# tcrt_0.net
KiCad netlist of a schematic drawn in Altium Designer
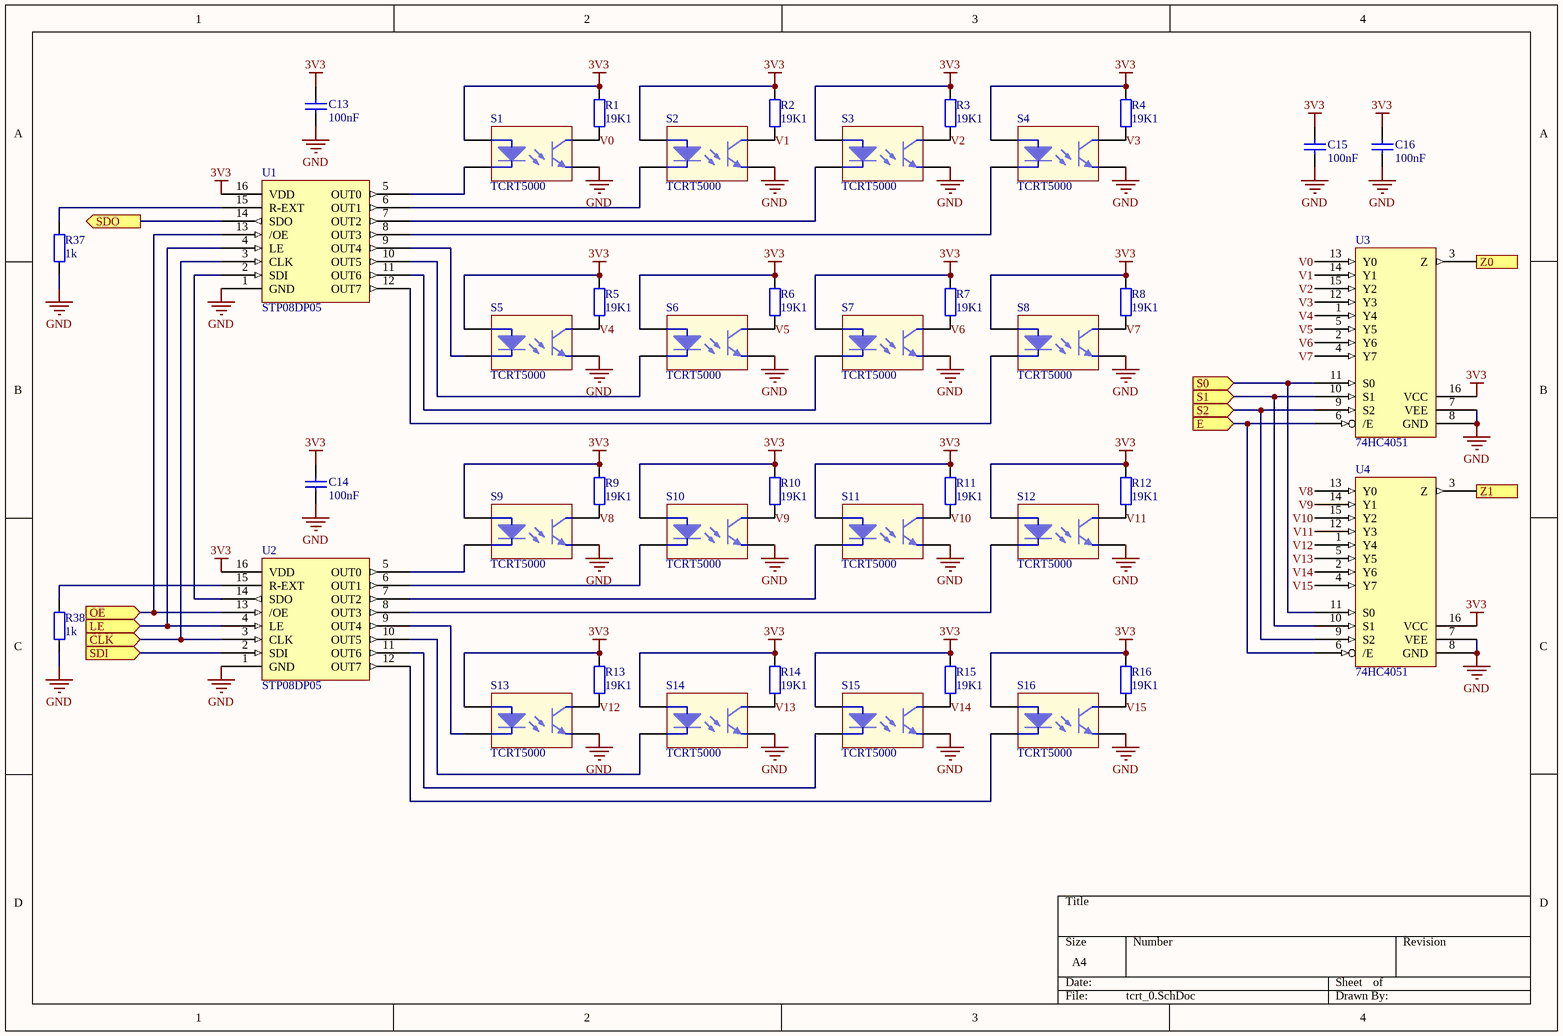
[diagram p0: tcrt_0.SchDoc]

(export (version "E")
  (design (tool "Eeschema 10.0.6"))
  (components
    (comp (ref "C13")
      (value "100nF")
      (footprint "FP_0805_CAP_085")
      (description "Capacitor")
      (libsource (lib "hallglib") (part "CAP"))
    )
    (comp (ref "C14")
      (value "100nF")
      (footprint "FP_0805_CAP_085")
      (description "Capacitor")
      (libsource (lib "hallglib") (part "CAP"))
    )
    (comp (ref "C15")
      (value "100nF")
      (footprint "FP_0805_CAP_085")
      (description "Capacitor")
      (libsource (lib "hallglib") (part "CAP"))
    )
    (comp (ref "C16")
      (value "100nF")
      (footprint "FP_0805_CAP_085")
      (description "Capacitor")
      (libsource (lib "hallglib") (part "CAP"))
    )
    (comp (ref "R1")
      (value "19K1")
      (footprint "FP_0805_RES")
      (description "Resistor")
      (libsource (lib "hallglib") (part "RES"))
    )
    (comp (ref "R2")
      (value "19K1")
      (footprint "FP_0805_RES")
      (description "Resistor")
      (libsource (lib "hallglib") (part "RES"))
    )
    (comp (ref "R3")
      (value "19K1")
      (footprint "FP_0805_RES")
      (description "Resistor")
      (libsource (lib "hallglib") (part "RES"))
    )
    (comp (ref "R4")
      (value "19K1")
      (footprint "FP_0805_RES")
      (description "Resistor")
      (libsource (lib "hallglib") (part "RES"))
    )
    (comp (ref "R5")
      (value "19K1")
      (footprint "FP_0805_RES")
      (description "Resistor")
      (libsource (lib "hallglib") (part "RES"))
    )
    (comp (ref "R6")
      (value "19K1")
      (footprint "FP_0805_RES")
      (description "Resistor")
      (libsource (lib "hallglib") (part "RES"))
    )
    (comp (ref "R7")
      (value "19K1")
      (footprint "FP_0805_RES")
      (description "Resistor")
      (libsource (lib "hallglib") (part "RES"))
    )
    (comp (ref "R8")
      (value "19K1")
      (footprint "FP_0805_RES")
      (description "Resistor")
      (libsource (lib "hallglib") (part "RES"))
    )
    (comp (ref "R9")
      (value "19K1")
      (footprint "FP_0805_RES")
      (description "Resistor")
      (libsource (lib "hallglib") (part "RES"))
    )
    (comp (ref "R10")
      (value "19K1")
      (footprint "FP_0805_RES")
      (description "Resistor")
      (libsource (lib "hallglib") (part "RES"))
    )
    (comp (ref "R11")
      (value "19K1")
      (footprint "FP_0805_RES")
      (description "Resistor")
      (libsource (lib "hallglib") (part "RES"))
    )
    (comp (ref "R12")
      (value "19K1")
      (footprint "FP_0805_RES")
      (description "Resistor")
      (libsource (lib "hallglib") (part "RES"))
    )
    (comp (ref "R13")
      (value "19K1")
      (footprint "FP_0805_RES")
      (description "Resistor")
      (libsource (lib "hallglib") (part "RES"))
    )
    (comp (ref "R14")
      (value "19K1")
      (footprint "FP_0805_RES")
      (description "Resistor")
      (libsource (lib "hallglib") (part "RES"))
    )
    (comp (ref "R15")
      (value "19K1")
      (footprint "FP_0805_RES")
      (description "Resistor")
      (libsource (lib "hallglib") (part "RES"))
    )
    (comp (ref "R16")
      (value "19K1")
      (footprint "FP_0805_RES")
      (description "Resistor")
      (libsource (lib "hallglib") (part "RES"))
    )
    (comp (ref "R37")
      (value "1k")
      (footprint "FP_0805_RES")
      (description "Resistor")
      (libsource (lib "") (part "RES_1"))
    )
    (comp (ref "R38")
      (value "1k")
      (footprint "FP_0805_RES")
      (description "Resistor")
      (libsource (lib "") (part "RES_1"))
    )
    (comp (ref "S1")
      (value "TCRT5000")
      (footprint "TCRT5000_nohole")
      (description "Reflective Optical Sensor")
      (libsource (lib "line-sensor") (part "TCRT5000"))
    )
    (comp (ref "S2")
      (value "TCRT5000")
      (footprint "TCRT5000_nohole")
      (description "Reflective Optical Sensor")
      (libsource (lib "line-sensor") (part "TCRT5000"))
    )
    (comp (ref "S3")
      (value "TCRT5000")
      (footprint "TCRT5000_nohole")
      (description "Reflective Optical Sensor")
      (libsource (lib "line-sensor") (part "TCRT5000"))
    )
    (comp (ref "S4")
      (value "TCRT5000")
      (footprint "TCRT5000_nohole")
      (description "Reflective Optical Sensor")
      (libsource (lib "line-sensor") (part "TCRT5000"))
    )
    (comp (ref "S5")
      (value "TCRT5000")
      (footprint "TCRT5000_nohole")
      (description "Reflective Optical Sensor")
      (libsource (lib "line-sensor") (part "TCRT5000"))
    )
    (comp (ref "S6")
      (value "TCRT5000")
      (footprint "TCRT5000_nohole")
      (description "Reflective Optical Sensor")
      (libsource (lib "line-sensor") (part "TCRT5000"))
    )
    (comp (ref "S7")
      (value "TCRT5000")
      (footprint "TCRT5000_nohole")
      (description "Reflective Optical Sensor")
      (libsource (lib "line-sensor") (part "TCRT5000"))
    )
    (comp (ref "S8")
      (value "TCRT5000")
      (footprint "TCRT5000_nohole")
      (description "Reflective Optical Sensor")
      (libsource (lib "line-sensor") (part "TCRT5000"))
    )
    (comp (ref "S9")
      (value "TCRT5000")
      (footprint "TCRT5000_nohole")
      (description "Reflective Optical Sensor")
      (libsource (lib "line-sensor") (part "TCRT5000"))
    )
    (comp (ref "S10")
      (value "TCRT5000")
      (footprint "TCRT5000_nohole")
      (description "Reflective Optical Sensor")
      (libsource (lib "line-sensor") (part "TCRT5000"))
    )
    (comp (ref "S11")
      (value "TCRT5000")
      (footprint "TCRT5000_nohole")
      (description "Reflective Optical Sensor")
      (libsource (lib "line-sensor") (part "TCRT5000"))
    )
    (comp (ref "S12")
      (value "TCRT5000")
      (footprint "TCRT5000_nohole")
      (description "Reflective Optical Sensor")
      (libsource (lib "line-sensor") (part "TCRT5000"))
    )
    (comp (ref "S13")
      (value "TCRT5000")
      (footprint "TCRT5000_nohole")
      (description "Reflective Optical Sensor")
      (libsource (lib "line-sensor") (part "TCRT5000"))
    )
    (comp (ref "S14")
      (value "TCRT5000")
      (footprint "TCRT5000_nohole")
      (description "Reflective Optical Sensor")
      (libsource (lib "line-sensor") (part "TCRT5000"))
    )
    (comp (ref "S15")
      (value "TCRT5000")
      (footprint "TCRT5000_nohole")
      (description "Reflective Optical Sensor")
      (libsource (lib "line-sensor") (part "TCRT5000"))
    )
    (comp (ref "S16")
      (value "TCRT5000")
      (footprint "TCRT5000_nohole")
      (description "Reflective Optical Sensor")
      (libsource (lib "line-sensor") (part "TCRT5000"))
    )
    (comp (ref "U1")
      (value "STP08DP05")
      (footprint "TSSOP16_2")
      (description "LED driver [8]")
      (libsource (lib "line-sensor") (part "STP08DP05"))
    )
    (comp (ref "U2")
      (value "STP08DP05")
      (footprint "TSSOP16_2")
      (description "LED driver [8]")
      (libsource (lib "line-sensor") (part "STP08DP05"))
    )
    (comp (ref "U3")
      (value "74HC4051")
      (footprint "TSSOP16_2")
      (description "Analog multiplexer")
      (libsource (lib "line-sensor") (part "74HC4051"))
    )
    (comp (ref "U4")
      (value "74HC4051")
      (footprint "TSSOP16_2")
      (description "Analog multiplexer")
      (libsource (lib "line-sensor") (part "74HC4051"))
    )
  )
  (nets
    (net (code "1") (name "/CLK") (class "Default")
      (node (ref "U1") (pin "3") (pinfunction "CLK_3") (pintype "input"))
      (node (ref "U2") (pin "3") (pinfunction "CLK_3") (pintype "input"))
    )
    (net (code "2") (name "/E") (class "Default")
      (node (ref "U3") (pin "6") (pinfunction "/E_6") (pintype "input"))
      (node (ref "U4") (pin "6") (pinfunction "/E_6") (pintype "input"))
    )
    (net (code "3") (name "/LE") (class "Default")
      (node (ref "U1") (pin "4") (pinfunction "LE_4") (pintype "input"))
      (node (ref "U2") (pin "4") (pinfunction "LE_4") (pintype "input"))
    )
    (net (code "4") (name "/OE") (class "Default")
      (node (ref "U1") (pin "13") (pinfunction "/OE_13") (pintype "input"))
      (node (ref "U2") (pin "13") (pinfunction "/OE_13") (pintype "input"))
    )
    (net (code "5") (name "/S0") (class "Default")
      (node (ref "U3") (pin "11") (pinfunction "S0_11") (pintype "input"))
      (node (ref "U4") (pin "11") (pinfunction "S0_11") (pintype "input"))
    )
    (net (code "6") (name "/S1") (class "Default")
      (node (ref "U3") (pin "10") (pinfunction "S1_10") (pintype "input"))
      (node (ref "U4") (pin "10") (pinfunction "S1_10") (pintype "input"))
    )
    (net (code "7") (name "/S2") (class "Default")
      (node (ref "U3") (pin "9") (pinfunction "S2_9") (pintype "input"))
      (node (ref "U4") (pin "9") (pinfunction "S2_9") (pintype "input"))
    )
    (net (code "8") (name "/SDI") (class "Default")
      (node (ref "U2") (pin "2") (pinfunction "SDI_2") (pintype "input"))
    )
    (net (code "9") (name "/SDO") (class "Default")
      (node (ref "U1") (pin "14") (pinfunction "SDO_14") (pintype "output"))
    )
    (net (code "10") (name "/V0") (class "Default")
      (node (ref "R1") (pin "1") (pinfunction "1_1") (pintype "passive"))
      (node (ref "S1") (pin "Coll") (pinfunction "C_Coll") (pintype "passive"))
      (node (ref "U3") (pin "13") (pinfunction "Y0_13") (pintype "input"))
    )
    (net (code "11") (name "/V1") (class "Default")
      (node (ref "R2") (pin "1") (pinfunction "1_1") (pintype "passive"))
      (node (ref "S2") (pin "Coll") (pinfunction "C_Coll") (pintype "passive"))
      (node (ref "U3") (pin "14") (pinfunction "Y1_14") (pintype "input"))
    )
    (net (code "12") (name "/V2") (class "Default")
      (node (ref "R3") (pin "1") (pinfunction "1_1") (pintype "passive"))
      (node (ref "S3") (pin "Coll") (pinfunction "C_Coll") (pintype "passive"))
      (node (ref "U3") (pin "15") (pinfunction "Y2_15") (pintype "input"))
    )
    (net (code "13") (name "/V3") (class "Default")
      (node (ref "R4") (pin "1") (pinfunction "1_1") (pintype "passive"))
      (node (ref "S4") (pin "Coll") (pinfunction "C_Coll") (pintype "passive"))
      (node (ref "U3") (pin "12") (pinfunction "Y3_12") (pintype "input"))
    )
    (net (code "14") (name "/V4") (class "Default")
      (node (ref "R5") (pin "1") (pinfunction "1_1") (pintype "passive"))
      (node (ref "S5") (pin "Coll") (pinfunction "C_Coll") (pintype "passive"))
      (node (ref "U3") (pin "1") (pinfunction "Y4_1") (pintype "input"))
    )
    (net (code "15") (name "/V5") (class "Default")
      (node (ref "R6") (pin "1") (pinfunction "1_1") (pintype "passive"))
      (node (ref "S6") (pin "Coll") (pinfunction "C_Coll") (pintype "passive"))
      (node (ref "U3") (pin "5") (pinfunction "Y5_5") (pintype "input"))
    )
    (net (code "16") (name "/V6") (class "Default")
      (node (ref "R7") (pin "1") (pinfunction "1_1") (pintype "passive"))
      (node (ref "S7") (pin "Coll") (pinfunction "C_Coll") (pintype "passive"))
      (node (ref "U3") (pin "2") (pinfunction "Y6_2") (pintype "input"))
    )
    (net (code "17") (name "/V7") (class "Default")
      (node (ref "R8") (pin "1") (pinfunction "1_1") (pintype "passive"))
      (node (ref "S8") (pin "Coll") (pinfunction "C_Coll") (pintype "passive"))
      (node (ref "U3") (pin "4") (pinfunction "Y7_4") (pintype "input"))
    )
    (net (code "18") (name "/V8") (class "Default")
      (node (ref "R9") (pin "1") (pinfunction "1_1") (pintype "passive"))
      (node (ref "S9") (pin "Coll") (pinfunction "C_Coll") (pintype "passive"))
      (node (ref "U4") (pin "13") (pinfunction "Y0_13") (pintype "input"))
    )
    (net (code "19") (name "/V9") (class "Default")
      (node (ref "R10") (pin "1") (pinfunction "1_1") (pintype "passive"))
      (node (ref "S10") (pin "Coll") (pinfunction "C_Coll") (pintype "passive"))
      (node (ref "U4") (pin "14") (pinfunction "Y1_14") (pintype "input"))
    )
    (net (code "20") (name "/V10") (class "Default")
      (node (ref "R11") (pin "1") (pinfunction "1_1") (pintype "passive"))
      (node (ref "S11") (pin "Coll") (pinfunction "C_Coll") (pintype "passive"))
      (node (ref "U4") (pin "15") (pinfunction "Y2_15") (pintype "input"))
    )
    (net (code "21") (name "/V11") (class "Default")
      (node (ref "R12") (pin "1") (pinfunction "1_1") (pintype "passive"))
      (node (ref "S12") (pin "Coll") (pinfunction "C_Coll") (pintype "passive"))
      (node (ref "U4") (pin "12") (pinfunction "Y3_12") (pintype "input"))
    )
    (net (code "22") (name "/V12") (class "Default")
      (node (ref "R13") (pin "1") (pinfunction "1_1") (pintype "passive"))
      (node (ref "S13") (pin "Coll") (pinfunction "C_Coll") (pintype "passive"))
      (node (ref "U4") (pin "1") (pinfunction "Y4_1") (pintype "input"))
    )
    (net (code "23") (name "/V13") (class "Default")
      (node (ref "R14") (pin "1") (pinfunction "1_1") (pintype "passive"))
      (node (ref "S14") (pin "Coll") (pinfunction "C_Coll") (pintype "passive"))
      (node (ref "U4") (pin "5") (pinfunction "Y5_5") (pintype "input"))
    )
    (net (code "24") (name "/V14") (class "Default")
      (node (ref "R15") (pin "1") (pinfunction "1_1") (pintype "passive"))
      (node (ref "S15") (pin "Coll") (pinfunction "C_Coll") (pintype "passive"))
      (node (ref "U4") (pin "2") (pinfunction "Y6_2") (pintype "input"))
    )
    (net (code "25") (name "/V15") (class "Default")
      (node (ref "R16") (pin "1") (pinfunction "1_1") (pintype "passive"))
      (node (ref "S16") (pin "Coll") (pinfunction "C_Coll") (pintype "passive"))
      (node (ref "U4") (pin "4") (pinfunction "Y7_4") (pintype "input"))
    )
    (net (code "26") (name "/Z0") (class "Default")
      (node (ref "U3") (pin "3") (pinfunction "Z_3") (pintype "output"))
    )
    (net (code "27") (name "/Z1") (class "Default")
      (node (ref "U4") (pin "3") (pinfunction "Z_3") (pintype "output"))
    )
    (net (code "28") (name "3V3") (class "Default")
      (node (ref "C13") (pin "2") (pinfunction "2_2") (pintype "passive"))
      (node (ref "C14") (pin "2") (pinfunction "2_2") (pintype "passive"))
      (node (ref "C15") (pin "2") (pinfunction "2_2") (pintype "passive"))
      (node (ref "C16") (pin "2") (pinfunction "2_2") (pintype "passive"))
      (node (ref "R1") (pin "2") (pinfunction "2_2") (pintype "passive"))
      (node (ref "R10") (pin "2") (pinfunction "2_2") (pintype "passive"))
      (node (ref "R11") (pin "2") (pinfunction "2_2") (pintype "passive"))
      (node (ref "R12") (pin "2") (pinfunction "2_2") (pintype "passive"))
      (node (ref "R13") (pin "2") (pinfunction "2_2") (pintype "passive"))
      (node (ref "R14") (pin "2") (pinfunction "2_2") (pintype "passive"))
      (node (ref "R15") (pin "2") (pinfunction "2_2") (pintype "passive"))
      (node (ref "R16") (pin "2") (pinfunction "2_2") (pintype "passive"))
      (node (ref "R2") (pin "2") (pinfunction "2_2") (pintype "passive"))
      (node (ref "R3") (pin "2") (pinfunction "2_2") (pintype "passive"))
      (node (ref "R4") (pin "2") (pinfunction "2_2") (pintype "passive"))
      (node (ref "R5") (pin "2") (pinfunction "2_2") (pintype "passive"))
      (node (ref "R6") (pin "2") (pinfunction "2_2") (pintype "passive"))
      (node (ref "R7") (pin "2") (pinfunction "2_2") (pintype "passive"))
      (node (ref "R8") (pin "2") (pinfunction "2_2") (pintype "passive"))
      (node (ref "R9") (pin "2") (pinfunction "2_2") (pintype "passive"))
      (node (ref "S1") (pin "A") (pinfunction "A_A") (pintype "passive"))
      (node (ref "S10") (pin "A") (pinfunction "A_A") (pintype "passive"))
      (node (ref "S11") (pin "A") (pinfunction "A_A") (pintype "passive"))
      (node (ref "S12") (pin "A") (pinfunction "A_A") (pintype "passive"))
      (node (ref "S13") (pin "A") (pinfunction "A_A") (pintype "passive"))
      (node (ref "S14") (pin "A") (pinfunction "A_A") (pintype "passive"))
      (node (ref "S15") (pin "A") (pinfunction "A_A") (pintype "passive"))
      (node (ref "S16") (pin "A") (pinfunction "A_A") (pintype "passive"))
      (node (ref "S2") (pin "A") (pinfunction "A_A") (pintype "passive"))
      (node (ref "S3") (pin "A") (pinfunction "A_A") (pintype "passive"))
      (node (ref "S4") (pin "A") (pinfunction "A_A") (pintype "passive"))
      (node (ref "S5") (pin "A") (pinfunction "A_A") (pintype "passive"))
      (node (ref "S6") (pin "A") (pinfunction "A_A") (pintype "passive"))
      (node (ref "S7") (pin "A") (pinfunction "A_A") (pintype "passive"))
      (node (ref "S8") (pin "A") (pinfunction "A_A") (pintype "passive"))
      (node (ref "S9") (pin "A") (pinfunction "A_A") (pintype "passive"))
      (node (ref "U1") (pin "16") (pinfunction "VDD_16") (pintype "passive"))
      (node (ref "U2") (pin "16") (pinfunction "VDD_16") (pintype "passive"))
      (node (ref "U3") (pin "16") (pinfunction "VCC_16") (pintype "power_in"))
      (node (ref "U4") (pin "16") (pinfunction "VCC_16") (pintype "power_in"))
    )
    (net (code "29") (name "GND") (class "Default")
      (node (ref "C13") (pin "1") (pinfunction "1_1") (pintype "passive"))
      (node (ref "C14") (pin "1") (pinfunction "1_1") (pintype "passive"))
      (node (ref "C15") (pin "1") (pinfunction "1_1") (pintype "passive"))
      (node (ref "C16") (pin "1") (pinfunction "1_1") (pintype "passive"))
      (node (ref "R37") (pin "2") (pinfunction "2_2") (pintype "passive"))
      (node (ref "R38") (pin "2") (pinfunction "2_2") (pintype "passive"))
      (node (ref "S1") (pin "E") (pinfunction "E_E") (pintype "passive"))
      (node (ref "S10") (pin "E") (pinfunction "E_E") (pintype "passive"))
      (node (ref "S11") (pin "E") (pinfunction "E_E") (pintype "passive"))
      (node (ref "S12") (pin "E") (pinfunction "E_E") (pintype "passive"))
      (node (ref "S13") (pin "E") (pinfunction "E_E") (pintype "passive"))
      (node (ref "S14") (pin "E") (pinfunction "E_E") (pintype "passive"))
      (node (ref "S15") (pin "E") (pinfunction "E_E") (pintype "passive"))
      (node (ref "S16") (pin "E") (pinfunction "E_E") (pintype "passive"))
      (node (ref "S2") (pin "E") (pinfunction "E_E") (pintype "passive"))
      (node (ref "S3") (pin "E") (pinfunction "E_E") (pintype "passive"))
      (node (ref "S4") (pin "E") (pinfunction "E_E") (pintype "passive"))
      (node (ref "S5") (pin "E") (pinfunction "E_E") (pintype "passive"))
      (node (ref "S6") (pin "E") (pinfunction "E_E") (pintype "passive"))
      (node (ref "S7") (pin "E") (pinfunction "E_E") (pintype "passive"))
      (node (ref "S8") (pin "E") (pinfunction "E_E") (pintype "passive"))
      (node (ref "S9") (pin "E") (pinfunction "E_E") (pintype "passive"))
      (node (ref "U1") (pin "1") (pinfunction "GND_1") (pintype "power_in"))
      (node (ref "U2") (pin "1") (pinfunction "GND_1") (pintype "power_in"))
      (node (ref "U3") (pin "7") (pinfunction "VEE_7") (pintype "power_in"))
      (node (ref "U3") (pin "8") (pinfunction "GND_8") (pintype "power_in"))
      (node (ref "U4") (pin "7") (pinfunction "VEE_7") (pintype "power_in"))
      (node (ref "U4") (pin "8") (pinfunction "GND_8") (pintype "power_in"))
    )
    (net (code "30") (name "Net-(S1-K)") (class "Default")
      (node (ref "S1") (pin "Cath") (pinfunction "K_Cath") (pintype "passive"))
      (node (ref "U1") (pin "5") (pinfunction "OUT0_5") (pintype "output"))
    )
    (net (code "31") (name "Net-(S2-K)") (class "Default")
      (node (ref "S2") (pin "Cath") (pinfunction "K_Cath") (pintype "passive"))
      (node (ref "U1") (pin "6") (pinfunction "OUT1_6") (pintype "output"))
    )
    (net (code "32") (name "Net-(S3-K)") (class "Default")
      (node (ref "S3") (pin "Cath") (pinfunction "K_Cath") (pintype "passive"))
      (node (ref "U1") (pin "7") (pinfunction "OUT2_7") (pintype "output"))
    )
    (net (code "33") (name "Net-(S4-K)") (class "Default")
      (node (ref "S4") (pin "Cath") (pinfunction "K_Cath") (pintype "passive"))
      (node (ref "U1") (pin "8") (pinfunction "OUT3_8") (pintype "output"))
    )
    (net (code "34") (name "Net-(S5-K)") (class "Default")
      (node (ref "S5") (pin "Cath") (pinfunction "K_Cath") (pintype "passive"))
      (node (ref "U1") (pin "9") (pinfunction "OUT4_9") (pintype "output"))
    )
    (net (code "35") (name "Net-(S6-K)") (class "Default")
      (node (ref "S6") (pin "Cath") (pinfunction "K_Cath") (pintype "passive"))
      (node (ref "U1") (pin "10") (pinfunction "OUT5_10") (pintype "output"))
    )
    (net (code "36") (name "Net-(S7-K)") (class "Default")
      (node (ref "S7") (pin "Cath") (pinfunction "K_Cath") (pintype "passive"))
      (node (ref "U1") (pin "11") (pinfunction "OUT6_11") (pintype "output"))
    )
    (net (code "37") (name "Net-(S8-K)") (class "Default")
      (node (ref "S8") (pin "Cath") (pinfunction "K_Cath") (pintype "passive"))
      (node (ref "U1") (pin "12") (pinfunction "OUT7_12") (pintype "output"))
    )
    (net (code "38") (name "Net-(S9-K)") (class "Default")
      (node (ref "S9") (pin "Cath") (pinfunction "K_Cath") (pintype "passive"))
      (node (ref "U2") (pin "5") (pinfunction "OUT0_5") (pintype "output"))
    )
    (net (code "39") (name "Net-(S10-K)") (class "Default")
      (node (ref "S10") (pin "Cath") (pinfunction "K_Cath") (pintype "passive"))
      (node (ref "U2") (pin "6") (pinfunction "OUT1_6") (pintype "output"))
    )
    (net (code "40") (name "Net-(S11-K)") (class "Default")
      (node (ref "S11") (pin "Cath") (pinfunction "K_Cath") (pintype "passive"))
      (node (ref "U2") (pin "7") (pinfunction "OUT2_7") (pintype "output"))
    )
    (net (code "41") (name "Net-(S12-K)") (class "Default")
      (node (ref "S12") (pin "Cath") (pinfunction "K_Cath") (pintype "passive"))
      (node (ref "U2") (pin "8") (pinfunction "OUT3_8") (pintype "output"))
    )
    (net (code "42") (name "Net-(S13-K)") (class "Default")
      (node (ref "S13") (pin "Cath") (pinfunction "K_Cath") (pintype "passive"))
      (node (ref "U2") (pin "9") (pinfunction "OUT4_9") (pintype "output"))
    )
    (net (code "43") (name "Net-(S14-K)") (class "Default")
      (node (ref "S14") (pin "Cath") (pinfunction "K_Cath") (pintype "passive"))
      (node (ref "U2") (pin "10") (pinfunction "OUT5_10") (pintype "output"))
    )
    (net (code "44") (name "Net-(S15-K)") (class "Default")
      (node (ref "S15") (pin "Cath") (pinfunction "K_Cath") (pintype "passive"))
      (node (ref "U2") (pin "11") (pinfunction "OUT6_11") (pintype "output"))
    )
    (net (code "45") (name "Net-(S16-K)") (class "Default")
      (node (ref "S16") (pin "Cath") (pinfunction "K_Cath") (pintype "passive"))
      (node (ref "U2") (pin "12") (pinfunction "OUT7_12") (pintype "output"))
    )
    (net (code "46") (name "Net-(U1-R-EXT)") (class "Default")
      (node (ref "R37") (pin "1") (pinfunction "1_1") (pintype "passive"))
      (node (ref "U1") (pin "15") (pinfunction "R-EXT_15") (pintype "passive"))
    )
    (net (code "47") (name "Net-(U1-SDI)") (class "Default")
      (node (ref "U1") (pin "2") (pinfunction "SDI_2") (pintype "input"))
      (node (ref "U2") (pin "14") (pinfunction "SDO_14") (pintype "output"))
    )
    (net (code "48") (name "Net-(U2-R-EXT)") (class "Default")
      (node (ref "R38") (pin "1") (pinfunction "1_1") (pintype "passive"))
      (node (ref "U2") (pin "15") (pinfunction "R-EXT_15") (pintype "passive"))
    )
  )
)
